# Mother.net
KiCad netlist of a schematic drawn in EAGLE
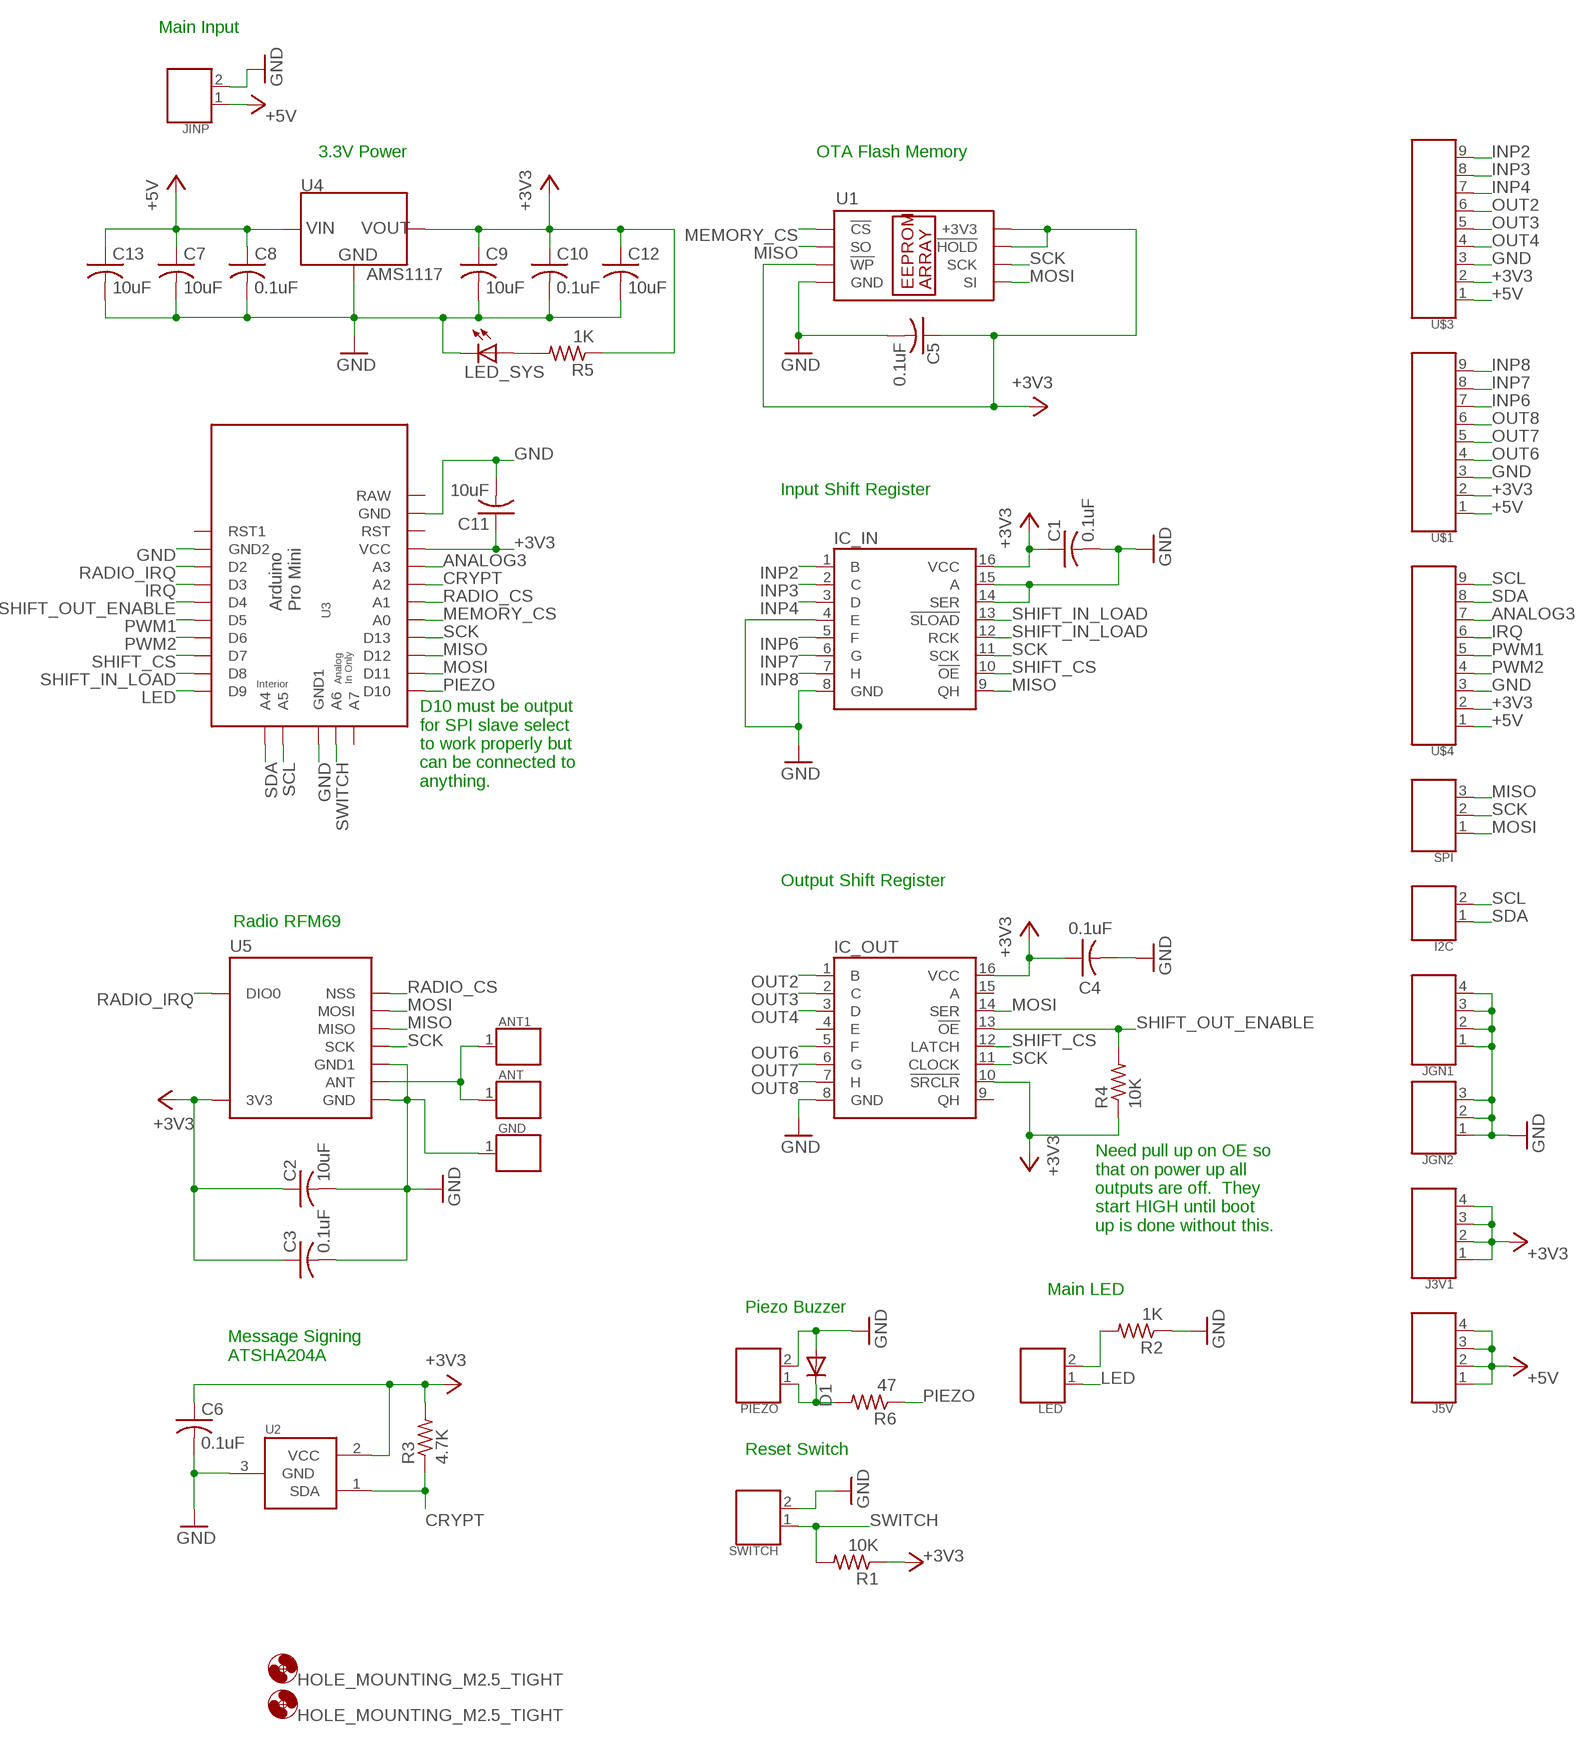
[diagram p0: schematic, sheet 1]

(export (version "E")
  (design (tool "Eeschema 10.0.6"))
  (components
    (comp (ref "ANT")
      (value "CONNECTOR_1DUPONT")
      (footprint "eagle-import:DUPONT_1")
      (libsource (lib "eagle-import") (part "CONNECTOR_1DUPONT"))
    )
    (comp (ref "ANT1")
      (value "CONNECTOR_1DUPONT")
      (footprint "eagle-import:DUPONT_1")
      (libsource (lib "eagle-import") (part "CONNECTOR_1DUPONT"))
    )
    (comp (ref "C1")
      (value "0.1uF")
      (footprint "eagle-import:CAP_0805")
      (libsource (lib "eagle-import") (part "CAP_0805"))
    )
    (comp (ref "C2")
      (value "10uF")
      (footprint "eagle-import:CAP_0805")
      (libsource (lib "eagle-import") (part "CAP_0805"))
    )
    (comp (ref "C3")
      (value "0.1uF")
      (footprint "eagle-import:CAP_0805")
      (libsource (lib "eagle-import") (part "CAP_0805"))
    )
    (comp (ref "C4")
      (value "0.1uF")
      (footprint "eagle-import:CAP_0805")
      (libsource (lib "eagle-import") (part "CAP_0805"))
    )
    (comp (ref "C5")
      (value "0.1uF")
      (footprint "eagle-import:CAP_0805")
      (libsource (lib "eagle-import") (part "CAP_0805"))
    )
    (comp (ref "C6")
      (value "0.1uF")
      (footprint "eagle-import:CAP_0805")
      (libsource (lib "eagle-import") (part "CAP_0805"))
    )
    (comp (ref "C7")
      (value "10uF")
      (footprint "eagle-import:CAP_0805")
      (libsource (lib "eagle-import") (part "CAP_0805"))
    )
    (comp (ref "C8")
      (value "0.1uF")
      (footprint "eagle-import:CAP_0805")
      (libsource (lib "eagle-import") (part "CAP_0805"))
    )
    (comp (ref "C9")
      (value "10uF")
      (footprint "eagle-import:CAP_0805")
      (libsource (lib "eagle-import") (part "CAP_0805"))
    )
    (comp (ref "C10")
      (value "0.1uF")
      (footprint "eagle-import:CAP_0805")
      (libsource (lib "eagle-import") (part "CAP_0805"))
    )
    (comp (ref "C11")
      (value "10uF")
      (footprint "eagle-import:CAP_0805")
      (libsource (lib "eagle-import") (part "CAP_0805"))
    )
    (comp (ref "C12")
      (value "10uF")
      (footprint "eagle-import:CAP_0805")
      (libsource (lib "eagle-import") (part "CAP_0805"))
    )
    (comp (ref "C13")
      (value "10uF")
      (footprint "eagle-import:CAP_0805")
      (libsource (lib "eagle-import") (part "CAP_0805"))
    )
    (comp (ref "D1")
      (value "DIODESOD323")
      (footprint "eagle-import:SOD323")
      (libsource (lib "eagle-import") (part "DIODESOD323"))
    )
    (comp (ref "GND")
      (value "CONNECTOR_1DUPONT")
      (footprint "eagle-import:DUPONT_1")
      (libsource (lib "eagle-import") (part "CONNECTOR_1DUPONT"))
    )
    (comp (ref "H1")
      (value "HOLE_MOUNTING_M2.5_TIGHT")
      (footprint "eagle-import:HOLE_M2.5PAN_TIGHT")
      (libsource (lib "eagle-import") (part "HOLE_MOUNTING_M2.5_TIGHT"))
    )
    (comp (ref "H2")
      (value "HOLE_MOUNTING_M2.5_TIGHT")
      (footprint "eagle-import:HOLE_M2.5PAN_TIGHT")
      (libsource (lib "eagle-import") (part "HOLE_MOUNTING_M2.5_TIGHT"))
    )
    (comp (ref "I2C")
      (value "CONNECTOR_2DUPONT")
      (footprint "eagle-import:DUPONT_2")
      (libsource (lib "eagle-import") (part "CONNECTOR_2DUPONT"))
    )
    (comp (ref "IC_IN")
      (value "IC_MM74HC589SO16")
      (footprint "eagle-import:SO16")
      (libsource (lib "eagle-import") (part "IC_MM74HC589SO16"))
    )
    (comp (ref "IC_OUT")
      (value "IC_SN74HC595")
      (footprint "eagle-import:SO16")
      (libsource (lib "eagle-import") (part "IC_SN74HC595"))
    )
    (comp (ref "J3V1")
      (value "CONNECTOR_4DUPONT")
      (footprint "eagle-import:DUPONT_4")
      (libsource (lib "eagle-import") (part "CONNECTOR_4DUPONT"))
    )
    (comp (ref "J5V")
      (value "CONNECTOR_4DUPONT")
      (footprint "eagle-import:DUPONT_4")
      (libsource (lib "eagle-import") (part "CONNECTOR_4DUPONT"))
    )
    (comp (ref "JGN1")
      (value "CONNECTOR_4DUPONT")
      (footprint "eagle-import:DUPONT_4")
      (libsource (lib "eagle-import") (part "CONNECTOR_4DUPONT"))
    )
    (comp (ref "JGN2")
      (value "CONNECTOR_3DUPONT")
      (footprint "eagle-import:DUPONT_3")
      (libsource (lib "eagle-import") (part "CONNECTOR_3DUPONT"))
    )
    (comp (ref "JINP")
      (value "CONNECTOR_2DUPONT")
      (footprint "eagle-import:DUPONT_2")
      (libsource (lib "eagle-import") (part "CONNECTOR_2DUPONT"))
    )
    (comp (ref "LED")
      (value "CONNECTOR_2DUPONT")
      (footprint "eagle-import:DUPONT_2")
      (libsource (lib "eagle-import") (part "CONNECTOR_2DUPONT"))
    )
    (comp (ref "LED_SYS")
      (value "LED")
      (footprint "eagle-import:LED_0805")
      (libsource (lib "eagle-import") (part "LED"))
    )
    (comp (ref "PIEZO")
      (value "CONNECTOR_2DUPONT")
      (footprint "eagle-import:DUPONT_2")
      (libsource (lib "eagle-import") (part "CONNECTOR_2DUPONT"))
    )
    (comp (ref "R1")
      (value "10K")
      (footprint "eagle-import:R_0805")
      (libsource (lib "eagle-import") (part "R_0805"))
    )
    (comp (ref "R2")
      (value "1K")
      (footprint "eagle-import:R_0805")
      (libsource (lib "eagle-import") (part "R_0805"))
    )
    (comp (ref "R3")
      (value "4.7K")
      (footprint "eagle-import:R_0805")
      (libsource (lib "eagle-import") (part "R_0805"))
    )
    (comp (ref "R4")
      (value "10K")
      (footprint "eagle-import:R_0805")
      (libsource (lib "eagle-import") (part "R_0805"))
    )
    (comp (ref "R5")
      (value "1K")
      (footprint "eagle-import:R_0805")
      (libsource (lib "eagle-import") (part "R_0805"))
    )
    (comp (ref "R6")
      (value "47")
      (footprint "eagle-import:R_0805")
      (libsource (lib "eagle-import") (part "R_0805"))
    )
    (comp (ref "SPI")
      (value "CONNECTOR_3DUPONT")
      (footprint "eagle-import:DUPONT_3")
      (libsource (lib "eagle-import") (part "CONNECTOR_3DUPONT"))
    )
    (comp (ref "SWITCH")
      (value "CONNECTOR_2DUPONT")
      (footprint "eagle-import:DUPONT_2")
      (libsource (lib "eagle-import") (part "CONNECTOR_2DUPONT"))
    )
    (comp (ref "U$1")
      (value "CONNECTOR_9DUP_MALE90")
      (footprint "eagle-import:DUPONT_MALE90_9")
      (libsource (lib "eagle-import") (part "CONNECTOR_9DUP_MALE90"))
    )
    (comp (ref "U$3")
      (value "CONNECTOR_9DUP_MALE90")
      (footprint "eagle-import:DUPONT_MALE90_9")
      (libsource (lib "eagle-import") (part "CONNECTOR_9DUP_MALE90"))
    )
    (comp (ref "U$4")
      (value "CONNECTOR_9DUPONT")
      (footprint "eagle-import:DUPONT_9")
      (libsource (lib "eagle-import") (part "CONNECTOR_9DUPONT"))
    )
    (comp (ref "U1")
      (value "IC_EEPROM")
      (footprint "eagle-import:SO-08")
      (libsource (lib "eagle-import") (part "IC_EEPROM"))
    )
    (comp (ref "U2")
      (value "IC_ATSHA204A_CRYPT")
      (footprint "eagle-import:SOT23-3")
      (libsource (lib "eagle-import") (part "IC_ATSHA204A_CRYPT"))
    )
    (comp (ref "U3")
      (value "ARD_PRO_MINI_CLONE_NOPROG")
      (footprint "eagle-import:PRO_MINI_CLONE_NO_PROG")
      (libsource (lib "eagle-import") (part "ARD_PRO_MINI_CLONE_NOPROG"))
    )
    (comp (ref "U4")
      (value "AMS1117")
      (footprint "eagle-import:SOT223")
      (libsource (lib "eagle-import") (part "IC_ASM1117_3.3V"))
    )
    (comp (ref "U5")
      (value "RADIO_RFM69W_MIN_PAD")
      (footprint "eagle-import:RFM69W_MIN_PAD")
      (libsource (lib "eagle-import") (part "RADIO_RFM69W_MIN_PAD"))
    )
  )
  (nets
    (net (code "1") (name "+3V3") (class "Default")
      (node (ref "C1") (pin "1") (pinfunction "1_1") (pintype "passive"))
      (node (ref "C10") (pin "1") (pinfunction "1_1") (pintype "passive"))
      (node (ref "C11") (pin "1") (pinfunction "1_1") (pintype "passive"))
      (node (ref "C12") (pin "1") (pinfunction "1_1") (pintype "passive"))
      (node (ref "C2") (pin "1") (pinfunction "1_1") (pintype "passive"))
      (node (ref "C3") (pin "1") (pinfunction "1_1") (pintype "passive"))
      (node (ref "C4") (pin "1") (pinfunction "1_1") (pintype "passive"))
      (node (ref "C5") (pin "1") (pinfunction "1_1") (pintype "passive"))
      (node (ref "C6") (pin "1") (pinfunction "1_1") (pintype "passive"))
      (node (ref "C9") (pin "1") (pinfunction "1_1") (pintype "passive"))
      (node (ref "IC_IN") (pin "16") (pinfunction "VCC_16") (pintype "power_in"))
      (node (ref "IC_OUT") (pin "10") (pinfunction "~{SRCLR}_10") (pintype "bidirectional"))
      (node (ref "IC_OUT") (pin "16") (pinfunction "VCC_16") (pintype "power_in"))
      (node (ref "J3V1") (pin "1") (pinfunction "1_1") (pintype "bidirectional"))
      (node (ref "J3V1") (pin "2") (pinfunction "2_2") (pintype "bidirectional"))
      (node (ref "J3V1") (pin "3") (pinfunction "3_3") (pintype "bidirectional"))
      (node (ref "J3V1") (pin "4") (pinfunction "4_4") (pintype "bidirectional"))
      (node (ref "R1") (pin "1") (pinfunction "1_1") (pintype "passive"))
      (node (ref "R3") (pin "2") (pinfunction "2_2") (pintype "passive"))
      (node (ref "R4") (pin "1") (pinfunction "1_1") (pintype "passive"))
      (node (ref "R5") (pin "1") (pinfunction "1_1") (pintype "passive"))
      (node (ref "U$1") (pin "2") (pinfunction "2_2") (pintype "bidirectional"))
      (node (ref "U$3") (pin "2") (pinfunction "2_2") (pintype "bidirectional"))
      (node (ref "U$4") (pin "2") (pinfunction "2_2") (pintype "bidirectional"))
      (node (ref "U1") (pin "3") (pinfunction "~{WP}_3") (pintype "bidirectional"))
      (node (ref "U1") (pin "7") (pinfunction "~{HOLD}_7") (pintype "bidirectional"))
      (node (ref "U1") (pin "8") (pinfunction "+3V3_8") (pintype "power_in"))
      (node (ref "U2") (pin "2") (pinfunction "VCC_2") (pintype "bidirectional"))
      (node (ref "U3") (pin "P$19") (pinfunction "VCC_P$19") (pintype "power_in"))
      (node (ref "U4") (pin "2") (pinfunction "VOUT_2") (pintype "power_in"))
      (node (ref "U4") (pin "4") (pinfunction "VOUT_4") (pintype "power_in"))
      (node (ref "U5") (pin "8") (pinfunction "3V3_8") (pintype "power_in"))
    )
    (net (code "2") (name "+5V") (class "Default")
      (node (ref "C13") (pin "1") (pinfunction "1_1") (pintype "passive"))
      (node (ref "C7") (pin "1") (pinfunction "1_1") (pintype "passive"))
      (node (ref "C8") (pin "1") (pinfunction "1_1") (pintype "passive"))
      (node (ref "J5V") (pin "1") (pinfunction "1_1") (pintype "bidirectional"))
      (node (ref "J5V") (pin "2") (pinfunction "2_2") (pintype "bidirectional"))
      (node (ref "J5V") (pin "3") (pinfunction "3_3") (pintype "bidirectional"))
      (node (ref "J5V") (pin "4") (pinfunction "4_4") (pintype "bidirectional"))
      (node (ref "JINP") (pin "1") (pinfunction "1_1") (pintype "bidirectional"))
      (node (ref "U$1") (pin "1") (pinfunction "1_1") (pintype "bidirectional"))
      (node (ref "U$3") (pin "1") (pinfunction "1_1") (pintype "bidirectional"))
      (node (ref "U$4") (pin "1") (pinfunction "1_1") (pintype "bidirectional"))
      (node (ref "U4") (pin "3") (pinfunction "VIN_3") (pintype "bidirectional"))
    )
    (net (code "3") (name "/ANALOG3") (class "Default")
      (node (ref "U$4") (pin "7") (pinfunction "7_7") (pintype "bidirectional"))
      (node (ref "U3") (pin "P$18") (pinfunction "A3_P$18") (pintype "bidirectional"))
    )
    (net (code "4") (name "/CRYPT") (class "Default")
      (node (ref "R3") (pin "1") (pinfunction "1_1") (pintype "passive"))
      (node (ref "U2") (pin "1") (pinfunction "SDA_1") (pintype "bidirectional"))
      (node (ref "U3") (pin "P$17") (pinfunction "A2_P$17") (pintype "bidirectional"))
    )
    (net (code "5") (name "/INP2") (class "Default")
      (node (ref "IC_IN") (pin "1") (pinfunction "B_1") (pintype "bidirectional"))
      (node (ref "U$3") (pin "9") (pinfunction "9_9") (pintype "bidirectional"))
    )
    (net (code "6") (name "/INP3") (class "Default")
      (node (ref "IC_IN") (pin "2") (pinfunction "C_2") (pintype "bidirectional"))
      (node (ref "U$3") (pin "8") (pinfunction "8_8") (pintype "bidirectional"))
    )
    (net (code "7") (name "/INP4") (class "Default")
      (node (ref "IC_IN") (pin "3") (pinfunction "D_3") (pintype "bidirectional"))
      (node (ref "U$3") (pin "7") (pinfunction "7_7") (pintype "bidirectional"))
    )
    (net (code "8") (name "/INP6") (class "Default")
      (node (ref "IC_IN") (pin "5") (pinfunction "F_5") (pintype "bidirectional"))
      (node (ref "U$1") (pin "7") (pinfunction "7_7") (pintype "bidirectional"))
    )
    (net (code "9") (name "/INP7") (class "Default")
      (node (ref "IC_IN") (pin "6") (pinfunction "G_6") (pintype "bidirectional"))
      (node (ref "U$1") (pin "8") (pinfunction "8_8") (pintype "bidirectional"))
    )
    (net (code "10") (name "/INP8") (class "Default")
      (node (ref "IC_IN") (pin "7") (pinfunction "H_7") (pintype "bidirectional"))
      (node (ref "U$1") (pin "9") (pinfunction "9_9") (pintype "bidirectional"))
    )
    (net (code "11") (name "/IRQ") (class "Default")
      (node (ref "U$4") (pin "6") (pinfunction "6_6") (pintype "bidirectional"))
      (node (ref "U3") (pin "P$4") (pinfunction "D3_P$4") (pintype "bidirectional"))
    )
    (net (code "12") (name "/LED") (class "Default")
      (node (ref "LED") (pin "1") (pinfunction "1_1") (pintype "bidirectional"))
      (node (ref "U3") (pin "P$10") (pinfunction "D9_P$10") (pintype "bidirectional"))
    )
    (net (code "13") (name "/MEMORY_CS") (class "Default")
      (node (ref "U1") (pin "1") (pinfunction "~{CS}_1") (pintype "bidirectional"))
      (node (ref "U3") (pin "P$15") (pinfunction "A0_P$15") (pintype "bidirectional"))
    )
    (net (code "14") (name "/MISO") (class "Default")
      (node (ref "IC_IN") (pin "9") (pinfunction "QH_9") (pintype "bidirectional"))
      (node (ref "SPI") (pin "3") (pinfunction "3_3") (pintype "bidirectional"))
      (node (ref "U1") (pin "2") (pinfunction "SO_2") (pintype "bidirectional"))
      (node (ref "U3") (pin "P$13") (pinfunction "D12_P$13") (pintype "bidirectional"))
      (node (ref "U5") (pin "13") (pinfunction "MISO_13") (pintype "bidirectional"))
    )
    (net (code "15") (name "/MOSI") (class "Default")
      (node (ref "IC_OUT") (pin "14") (pinfunction "SER_14") (pintype "bidirectional"))
      (node (ref "SPI") (pin "1") (pinfunction "1_1") (pintype "bidirectional"))
      (node (ref "U1") (pin "5") (pinfunction "SI_5") (pintype "bidirectional"))
      (node (ref "U3") (pin "P$12") (pinfunction "D11_P$12") (pintype "bidirectional"))
      (node (ref "U5") (pin "14") (pinfunction "MOSI_14") (pintype "bidirectional"))
    )
    (net (code "16") (name "/OUT2") (class "Default")
      (node (ref "IC_OUT") (pin "1") (pinfunction "B_1") (pintype "bidirectional"))
      (node (ref "U$3") (pin "6") (pinfunction "6_6") (pintype "bidirectional"))
    )
    (net (code "17") (name "/OUT3") (class "Default")
      (node (ref "IC_OUT") (pin "2") (pinfunction "C_2") (pintype "bidirectional"))
      (node (ref "U$3") (pin "5") (pinfunction "5_5") (pintype "bidirectional"))
    )
    (net (code "18") (name "/OUT4") (class "Default")
      (node (ref "IC_OUT") (pin "3") (pinfunction "D_3") (pintype "bidirectional"))
      (node (ref "U$3") (pin "4") (pinfunction "4_4") (pintype "bidirectional"))
    )
    (net (code "19") (name "/OUT6") (class "Default")
      (node (ref "IC_OUT") (pin "5") (pinfunction "F_5") (pintype "bidirectional"))
      (node (ref "U$1") (pin "4") (pinfunction "4_4") (pintype "bidirectional"))
    )
    (net (code "20") (name "/OUT7") (class "Default")
      (node (ref "IC_OUT") (pin "6") (pinfunction "G_6") (pintype "bidirectional"))
      (node (ref "U$1") (pin "5") (pinfunction "5_5") (pintype "bidirectional"))
    )
    (net (code "21") (name "/OUT8") (class "Default")
      (node (ref "IC_OUT") (pin "7") (pinfunction "H_7") (pintype "bidirectional"))
      (node (ref "U$1") (pin "6") (pinfunction "6_6") (pintype "bidirectional"))
    )
    (net (code "22") (name "/PIEZO") (class "Default")
      (node (ref "R6") (pin "1") (pinfunction "1_1") (pintype "passive"))
      (node (ref "U3") (pin "P$11") (pinfunction "D10_P$11") (pintype "bidirectional"))
    )
    (net (code "23") (name "/PWM1") (class "Default")
      (node (ref "U$4") (pin "5") (pinfunction "5_5") (pintype "bidirectional"))
      (node (ref "U3") (pin "P$6") (pinfunction "D5_P$6") (pintype "bidirectional"))
    )
    (net (code "24") (name "/PWM2") (class "Default")
      (node (ref "U$4") (pin "4") (pinfunction "4_4") (pintype "bidirectional"))
      (node (ref "U3") (pin "P$7") (pinfunction "D6_P$7") (pintype "bidirectional"))
    )
    (net (code "25") (name "/RADIO_CS") (class "Default")
      (node (ref "U3") (pin "P$16") (pinfunction "A1_P$16") (pintype "bidirectional"))
      (node (ref "U5") (pin "15") (pinfunction "NSS_15") (pintype "bidirectional"))
    )
    (net (code "26") (name "/RADIO_IRQ") (class "Default")
      (node (ref "U3") (pin "P$3") (pinfunction "D2_P$3") (pintype "bidirectional"))
      (node (ref "U5") (pin "2") (pinfunction "DIO0_2") (pintype "bidirectional"))
    )
    (net (code "27") (name "/RAW") (class "Default")
      (node (ref "U3") (pin "P$22") (pinfunction "RAW_P$22") (pintype "power_in"))
    )
    (net (code "28") (name "/SCK") (class "Default")
      (node (ref "IC_IN") (pin "11") (pinfunction "SCK_11") (pintype "bidirectional"))
      (node (ref "IC_OUT") (pin "11") (pinfunction "CLOCK_11") (pintype "bidirectional"))
      (node (ref "SPI") (pin "2") (pinfunction "2_2") (pintype "bidirectional"))
      (node (ref "U1") (pin "6") (pinfunction "SCK_6") (pintype "bidirectional"))
      (node (ref "U3") (pin "P$14") (pinfunction "D13_P$14") (pintype "bidirectional"))
      (node (ref "U5") (pin "12") (pinfunction "SCK_12") (pintype "bidirectional"))
    )
    (net (code "29") (name "/SCL") (class "Default")
      (node (ref "I2C") (pin "2") (pinfunction "2_2") (pintype "bidirectional"))
      (node (ref "U$4") (pin "9") (pinfunction "9_9") (pintype "bidirectional"))
      (node (ref "U3") (pin "P$24") (pinfunction "A5_P$24") (pintype "bidirectional"))
    )
    (net (code "30") (name "/SDA") (class "Default")
      (node (ref "I2C") (pin "1") (pinfunction "1_1") (pintype "bidirectional"))
      (node (ref "U$4") (pin "8") (pinfunction "8_8") (pintype "bidirectional"))
      (node (ref "U3") (pin "P$23") (pinfunction "A4_P$23") (pintype "bidirectional"))
    )
    (net (code "31") (name "/SHIFT_CS") (class "Default")
      (node (ref "IC_IN") (pin "10") (pinfunction "~{OE}_10") (pintype "bidirectional"))
      (node (ref "IC_OUT") (pin "12") (pinfunction "LATCH_12") (pintype "bidirectional"))
      (node (ref "U3") (pin "P$8") (pinfunction "D7_P$8") (pintype "bidirectional"))
    )
    (net (code "32") (name "/SHIFT_IN_LOAD") (class "Default")
      (node (ref "IC_IN") (pin "12") (pinfunction "RCK_12") (pintype "bidirectional"))
      (node (ref "IC_IN") (pin "13") (pinfunction "~{SLOAD}_13") (pintype "bidirectional"))
      (node (ref "U3") (pin "P$9") (pinfunction "D8_P$9") (pintype "bidirectional"))
    )
    (net (code "33") (name "/SHIFT_OUT_ENABLE") (class "Default")
      (node (ref "IC_OUT") (pin "13") (pinfunction "~{OE}_13") (pintype "bidirectional"))
      (node (ref "R4") (pin "2") (pinfunction "2_2") (pintype "passive"))
      (node (ref "U3") (pin "P$5") (pinfunction "D4_P$5") (pintype "bidirectional"))
    )
    (net (code "34") (name "/SWITCH") (class "Default")
      (node (ref "R1") (pin "2") (pinfunction "2_2") (pintype "passive"))
      (node (ref "SWITCH") (pin "1") (pinfunction "1_1") (pintype "bidirectional"))
      (node (ref "U3") (pin "P$26") (pinfunction "A6_P$26") (pintype "bidirectional"))
    )
    (net (code "35") (name "GND") (class "Default")
      (node (ref "C1") (pin "2") (pinfunction "2_2") (pintype "passive"))
      (node (ref "C10") (pin "2") (pinfunction "2_2") (pintype "passive"))
      (node (ref "C11") (pin "2") (pinfunction "2_2") (pintype "passive"))
      (node (ref "C12") (pin "2") (pinfunction "2_2") (pintype "passive"))
      (node (ref "C13") (pin "2") (pinfunction "2_2") (pintype "passive"))
      (node (ref "C2") (pin "2") (pinfunction "2_2") (pintype "passive"))
      (node (ref "C3") (pin "2") (pinfunction "2_2") (pintype "passive"))
      (node (ref "C4") (pin "2") (pinfunction "2_2") (pintype "passive"))
      (node (ref "C5") (pin "2") (pinfunction "2_2") (pintype "passive"))
      (node (ref "C6") (pin "2") (pinfunction "2_2") (pintype "passive"))
      (node (ref "C7") (pin "2") (pinfunction "2_2") (pintype "passive"))
      (node (ref "C8") (pin "2") (pinfunction "2_2") (pintype "passive"))
      (node (ref "C9") (pin "2") (pinfunction "2_2") (pintype "passive"))
      (node (ref "D1") (pin "A") (pinfunction "A_A") (pintype "passive"))
      (node (ref "GND") (pin "1") (pinfunction "1_1") (pintype "bidirectional"))
      (node (ref "IC_IN") (pin "14") (pinfunction "SER_14") (pintype "bidirectional"))
      (node (ref "IC_IN") (pin "15") (pinfunction "A_15") (pintype "bidirectional"))
      (node (ref "IC_IN") (pin "4") (pinfunction "E_4") (pintype "bidirectional"))
      (node (ref "IC_IN") (pin "8") (pinfunction "GND_8") (pintype "power_in"))
      (node (ref "IC_OUT") (pin "8") (pinfunction "GND_8") (pintype "power_in"))
      (node (ref "JGN1") (pin "1") (pinfunction "1_1") (pintype "bidirectional"))
      (node (ref "JGN1") (pin "2") (pinfunction "2_2") (pintype "bidirectional"))
      (node (ref "JGN1") (pin "3") (pinfunction "3_3") (pintype "bidirectional"))
      (node (ref "JGN1") (pin "4") (pinfunction "4_4") (pintype "bidirectional"))
      (node (ref "JGN2") (pin "1") (pinfunction "1_1") (pintype "bidirectional"))
      (node (ref "JGN2") (pin "2") (pinfunction "2_2") (pintype "bidirectional"))
      (node (ref "JGN2") (pin "3") (pinfunction "3_3") (pintype "bidirectional"))
      (node (ref "JINP") (pin "2") (pinfunction "2_2") (pintype "bidirectional"))
      (node (ref "LED_SYS") (pin "2") (pinfunction "C_2") (pintype "passive"))
      (node (ref "PIEZO") (pin "2") (pinfunction "2_2") (pintype "bidirectional"))
      (node (ref "R2") (pin "1") (pinfunction "1_1") (pintype "passive"))
      (node (ref "SWITCH") (pin "2") (pinfunction "2_2") (pintype "bidirectional"))
      (node (ref "U$1") (pin "3") (pinfunction "3_3") (pintype "bidirectional"))
      (node (ref "U$3") (pin "3") (pinfunction "3_3") (pintype "bidirectional"))
      (node (ref "U$4") (pin "3") (pinfunction "3_3") (pintype "bidirectional"))
      (node (ref "U1") (pin "4") (pinfunction "GND_4") (pintype "power_in"))
      (node (ref "U2") (pin "3") (pinfunction "GND_3") (pintype "bidirectional"))
      (node (ref "U3") (pin "P$2") (pinfunction "GND2_P$2") (pintype "power_in"))
      (node (ref "U3") (pin "P$21") (pinfunction "GND_P$21") (pintype "power_in"))
      (node (ref "U3") (pin "P$27") (pinfunction "GND1_P$27") (pintype "power_in"))
      (node (ref "U4") (pin "1") (pinfunction "GND_1") (pintype "power_in"))
      (node (ref "U5") (pin "11") (pinfunction "GND1_11") (pintype "power_in"))
      (node (ref "U5") (pin "9") (pinfunction "GND_9") (pintype "power_in"))
    )
    (net (code "36") (name "Net-(D1-PadC)") (class "Default")
      (node (ref "D1") (pin "C") (pinfunction "C_C") (pintype "passive"))
      (node (ref "PIEZO") (pin "1") (pinfunction "1_1") (pintype "bidirectional"))
      (node (ref "R6") (pin "2") (pinfunction "2_2") (pintype "passive"))
    )
    (net (code "37") (name "Net-(LED-Pad2)") (class "Default")
      (node (ref "LED") (pin "2") (pinfunction "2_2") (pintype "bidirectional"))
      (node (ref "R2") (pin "2") (pinfunction "2_2") (pintype "passive"))
    )
    (net (code "38") (name "Net-(LED_SYS-A)") (class "Default")
      (node (ref "LED_SYS") (pin "1") (pinfunction "A_1") (pintype "passive"))
      (node (ref "R5") (pin "2") (pinfunction "2_2") (pintype "passive"))
    )
    (net (code "39") (name "Net-(U5-ANT)") (class "Default")
      (node (ref "ANT") (pin "1") (pinfunction "1_1") (pintype "bidirectional"))
      (node (ref "ANT1") (pin "1") (pinfunction "1_1") (pintype "bidirectional"))
      (node (ref "U5") (pin "10") (pinfunction "ANT_10") (pintype "bidirectional"))
    )
    (net (code "40") (name "unconnected-(IC_OUT-A-Pad15)") (class "Default")
      (node (ref "IC_OUT") (pin "15") (pinfunction "A_15") (pintype "bidirectional"))
    )
    (net (code "41") (name "unconnected-(IC_OUT-E-Pad4)") (class "Default")
      (node (ref "IC_OUT") (pin "4") (pinfunction "E_4") (pintype "bidirectional"))
    )
    (net (code "42") (name "unconnected-(IC_OUT-QH-Pad9)") (class "Default")
      (node (ref "IC_OUT") (pin "9") (pinfunction "QH_9") (pintype "bidirectional"))
    )
    (net (code "43") (name "unconnected-(U3-A7-PadP$25)") (class "Default")
      (node (ref "U3") (pin "P$25") (pinfunction "A7_P$25") (pintype "bidirectional"))
    )
    (net (code "44") (name "unconnected-(U3-RST-PadP$20)") (class "Default")
      (node (ref "U3") (pin "P$20") (pinfunction "RST_P$20") (pintype "bidirectional"))
    )
    (net (code "45") (name "unconnected-(U3-RST1-PadP$1)") (class "Default")
      (node (ref "U3") (pin "P$1") (pinfunction "RST1_P$1") (pintype "bidirectional"))
    )
  )
)
